# NRF51822_schematic.net
KiCad netlist of a schematic drawn in Altium Designer
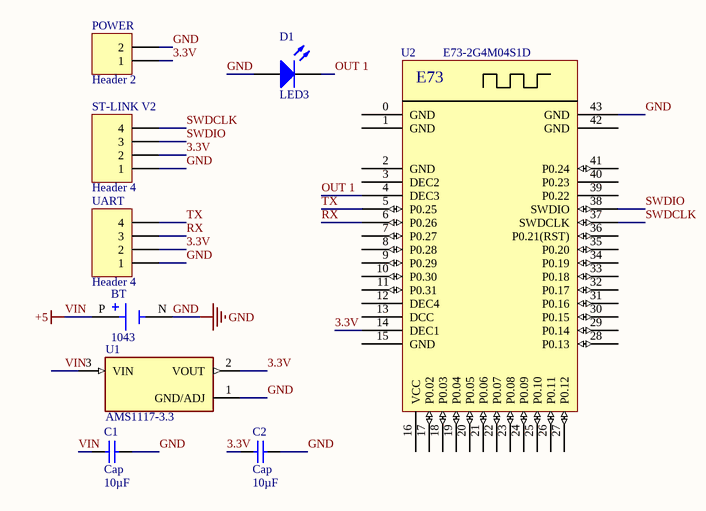
[diagram p0: NRF51822 schematic.SchDoc]

(export (version "E")
  (design (tool "Eeschema 10.0.6"))
  (components
    (comp (ref "BT")
      (value "1043")
      (footprint "BAT_1043")
      (description "THM Holder for 18650 Battery")
      (fields (field (name "MF") "Keystone Electronics"))
      (libsource (lib "1043") (part "1043"))
    )
    (comp (ref "C1")
      (value "Cap")
      (footprint "RAD-0.3")
      (description "Capacitor")
      (fields (field (name "ALTIUM_VALUE") "10µF") (field (name "PUBLISHER") "Altium Limited"))
      (libsource (lib "Miscellaneous Devices") (part "Cap"))
    )
    (comp (ref "C2")
      (value "Cap")
      (footprint "RAD-0.3")
      (description "Capacitor")
      (fields (field (name "ALTIUM_VALUE") "10µF") (field (name "PUBLISHER") "Altium Limited"))
      (libsource (lib "Miscellaneous Devices") (part "Cap"))
    )
    (comp (ref "D1")
      (value "LED3")
      (footprint "3.5X2.8X1.9")
      (description "Typical BLUE SiC LED")
      (fields (field (name "PUBLISHER") "Altium Limited"))
      (libsource (lib "Miscellaneous Devices") (part "LED3"))
    )
    (comp (ref "POWER")
      (value "Header 2")
      (footprint "HDR1X2")
      (description "Header, 2-Pin")
      (fields (field (name "PUBLISHER") "Altium Limited"))
      (libsource (lib "Miscellaneous Connectors") (part "Header 2"))
    )
    (comp (ref "ST-LINK V2")
      (value "Header 4")
      (footprint "HDR1X4")
      (description "Header, 4-Pin")
      (fields (field (name "PUBLISHER") "Altium Limited"))
      (libsource (lib "Miscellaneous Connectors") (part "Header 4"))
    )
    (comp (ref "U1")
      (value "AMS1117-3.3")
      (footprint "SOT229P700X180-4N")
      (description "Sot223/Pkg 1-Amp 3.3-Volt Low Drop Out Voltage Regulatator")
      (fields (field (name "MF") "Advanced Monolithic Systems"))
      (libsource (lib "AMS1117-3.3") (part "AMS1117-3.3"))
    )
    (comp (ref "U2")
      (value "E73-2G4M04S1D")
      (footprint "E73-2G4M04S1D")
      (libsource (lib "E73-2G4M04S1D-Chengdu Ebyte Electronic Technology-Symbol-Altium-19183") (part "E73-2G4M04S1D"))
    )
    (comp (ref "UART")
      (value "Header 4")
      (footprint "HDR1X4")
      (description "Header, 4-Pin")
      (fields (field (name "PUBLISHER") "Altium Limited"))
      (libsource (lib "Miscellaneous Connectors") (part "Header 4"))
    )
  )
  (nets
    (net (code "1") (name "+5") (class "Default")
      (node (ref "BT") (pin "P") (pinfunction "POS_P") (pintype "passive"))
      (node (ref "C1") (pin "1") (pinfunction "1_1") (pintype "passive"))
      (node (ref "U1") (pin "3") (pinfunction "VIN_3") (pintype "input"))
    )
    (net (code "2") (name "/3.3V") (class "Default")
      (node (ref "C2") (pin "1") (pinfunction "1_1") (pintype "passive"))
      (node (ref "POWER") (pin "1") (pinfunction "1_1") (pintype "passive"))
      (node (ref "ST-LINK V2") (pin "2") (pinfunction "2_2") (pintype "passive"))
      (node (ref "U1") (pin "2") (pinfunction "VOUT_2") (pintype "output"))
      (node (ref "U2") (pin "14") (pinfunction "DEC1_14") (pintype "passive"))
      (node (ref "UART") (pin "2") (pinfunction "2_2") (pintype "passive"))
    )
    (net (code "4") (name "/OUT 1") (class "Default")
      (node (ref "D1") (pin "2") (pinfunction "K_2") (pintype "passive"))
      (node (ref "U2") (pin "4") (pinfunction "DEC3_4") (pintype "passive"))
    )
    (net (code "5") (name "/RX") (class "Default")
      (node (ref "U2") (pin "6") (pinfunction "P0.26_6") (pintype "bidirectional"))
      (node (ref "UART") (pin "3") (pinfunction "3_3") (pintype "passive"))
    )
    (net (code "6") (name "/SWDCLK") (class "Default")
      (node (ref "ST-LINK V2") (pin "4") (pinfunction "4_4") (pintype "passive"))
      (node (ref "U2") (pin "37") (pinfunction "SWDCLK_37") (pintype "bidirectional"))
    )
    (net (code "7") (name "/SWDIO") (class "Default")
      (node (ref "ST-LINK V2") (pin "3") (pinfunction "3_3") (pintype "passive"))
      (node (ref "U2") (pin "38") (pinfunction "SWDIO_38") (pintype "bidirectional"))
    )
    (net (code "8") (name "/TX") (class "Default")
      (node (ref "U2") (pin "5") (pinfunction "P0.25_5") (pintype "bidirectional"))
      (node (ref "UART") (pin "4") (pinfunction "4_4") (pintype "passive"))
    )
    (net (code "9") (name "GND") (class "Default")
      (node (ref "BT") (pin "N") (pinfunction "NEG_N") (pintype "passive"))
      (node (ref "C1") (pin "2") (pinfunction "2_2") (pintype "passive"))
      (node (ref "C2") (pin "2") (pinfunction "2_2") (pintype "passive"))
      (node (ref "D1") (pin "1") (pinfunction "A_1") (pintype "passive"))
      (node (ref "POWER") (pin "2") (pinfunction "2_2") (pintype "passive"))
      (node (ref "ST-LINK V2") (pin "1") (pinfunction "1_1") (pintype "passive"))
      (node (ref "U1") (pin "1") (pinfunction "GND/ADJ_1") (pintype "power_in"))
      (node (ref "U2") (pin "43") (pinfunction "GND_43") (pintype "passive"))
      (node (ref "UART") (pin "1") (pinfunction "1_1") (pintype "passive"))
    )
    (net (code "10") (name "unconnected-(U2-DCC-Pad13)") (class "Default")
      (node (ref "U2") (pin "13") (pinfunction "DCC_13") (pintype "passive"))
    )
    (net (code "11") (name "unconnected-(U2-DEC2-Pad3)") (class "Default")
      (node (ref "U2") (pin "3") (pinfunction "DEC2_3") (pintype "passive"))
    )
    (net (code "12") (name "unconnected-(U2-DEC4-Pad12)") (class "Default")
      (node (ref "U2") (pin "12") (pinfunction "DEC4_12") (pintype "passive"))
    )
    (net (code "13") (name "unconnected-(U2-GND-Pad0)") (class "Default")
      (node (ref "U2") (pin "0") (pinfunction "GND_0") (pintype "passive"))
    )
    (net (code "14") (name "unconnected-(U2-GND-Pad1)") (class "Default")
      (node (ref "U2") (pin "1") (pinfunction "GND_1") (pintype "passive"))
    )
    (net (code "15") (name "unconnected-(U2-GND-Pad2)") (class "Default")
      (node (ref "U2") (pin "2") (pinfunction "GND_2") (pintype "passive"))
    )
    (net (code "16") (name "unconnected-(U2-GND-Pad15)") (class "Default")
      (node (ref "U2") (pin "15") (pinfunction "GND_15") (pintype "passive"))
    )
    (net (code "17") (name "unconnected-(U2-GND-Pad42)") (class "Default")
      (node (ref "U2") (pin "42") (pinfunction "GND_42") (pintype "passive"))
    )
    (net (code "18") (name "unconnected-(U2-P0.02-Pad17)") (class "Default")
      (node (ref "U2") (pin "17") (pinfunction "P0.02_17") (pintype "bidirectional"))
    )
    (net (code "19") (name "unconnected-(U2-P0.03-Pad18)") (class "Default")
      (node (ref "U2") (pin "18") (pinfunction "P0.03_18") (pintype "bidirectional"))
    )
    (net (code "20") (name "unconnected-(U2-P0.04-Pad19)") (class "Default")
      (node (ref "U2") (pin "19") (pinfunction "P0.04_19") (pintype "bidirectional"))
    )
    (net (code "21") (name "unconnected-(U2-P0.05-Pad20)") (class "Default")
      (node (ref "U2") (pin "20") (pinfunction "P0.05_20") (pintype "bidirectional"))
    )
    (net (code "22") (name "unconnected-(U2-P0.06-Pad21)") (class "Default")
      (node (ref "U2") (pin "21") (pinfunction "P0.06_21") (pintype "bidirectional"))
    )
    (net (code "23") (name "unconnected-(U2-P0.07-Pad22)") (class "Default")
      (node (ref "U2") (pin "22") (pinfunction "P0.07_22") (pintype "bidirectional"))
    )
    (net (code "24") (name "unconnected-(U2-P0.08-Pad23)") (class "Default")
      (node (ref "U2") (pin "23") (pinfunction "P0.08_23") (pintype "bidirectional"))
    )
    (net (code "25") (name "unconnected-(U2-P0.09-Pad24)") (class "Default")
      (node (ref "U2") (pin "24") (pinfunction "P0.09_24") (pintype "bidirectional"))
    )
    (net (code "26") (name "unconnected-(U2-P0.10-Pad25)") (class "Default")
      (node (ref "U2") (pin "25") (pinfunction "P0.10_25") (pintype "bidirectional"))
    )
    (net (code "27") (name "unconnected-(U2-P0.11-Pad26)") (class "Default")
      (node (ref "U2") (pin "26") (pinfunction "P0.11_26") (pintype "bidirectional"))
    )
    (net (code "28") (name "unconnected-(U2-P0.12-Pad27)") (class "Default")
      (node (ref "U2") (pin "27") (pinfunction "P0.12_27") (pintype "bidirectional"))
    )
    (net (code "29") (name "unconnected-(U2-P0.13-Pad28)") (class "Default")
      (node (ref "U2") (pin "28") (pinfunction "P0.13_28") (pintype "bidirectional"))
    )
    (net (code "30") (name "unconnected-(U2-P0.14-Pad29)") (class "Default")
      (node (ref "U2") (pin "29") (pinfunction "P0.14_29") (pintype "bidirectional"))
    )
    (net (code "31") (name "unconnected-(U2-P0.15-Pad30)") (class "Default")
      (node (ref "U2") (pin "30") (pinfunction "P0.15_30") (pintype "bidirectional"))
    )
    (net (code "32") (name "unconnected-(U2-P0.16-Pad31)") (class "Default")
      (node (ref "U2") (pin "31") (pinfunction "P0.16_31") (pintype "bidirectional"))
    )
    (net (code "33") (name "unconnected-(U2-P0.17-Pad32)") (class "Default")
      (node (ref "U2") (pin "32") (pinfunction "P0.17_32") (pintype "bidirectional"))
    )
    (net (code "34") (name "unconnected-(U2-P0.18-Pad33)") (class "Default")
      (node (ref "U2") (pin "33") (pinfunction "P0.18_33") (pintype "bidirectional"))
    )
    (net (code "35") (name "unconnected-(U2-P0.19-Pad34)") (class "Default")
      (node (ref "U2") (pin "34") (pinfunction "P0.19_34") (pintype "bidirectional"))
    )
    (net (code "36") (name "unconnected-(U2-P0.20-Pad35)") (class "Default")
      (node (ref "U2") (pin "35") (pinfunction "P0.20_35") (pintype "bidirectional"))
    )
    (net (code "37") (name "unconnected-(U2-P0.21(RST)-Pad36)") (class "Default")
      (node (ref "U2") (pin "36") (pinfunction "P0.21(RST)_36") (pintype "bidirectional"))
    )
    (net (code "38") (name "unconnected-(U2-P0.22-Pad39)") (class "Default")
      (node (ref "U2") (pin "39") (pinfunction "P0.22_39") (pintype "passive"))
    )
    (net (code "39") (name "unconnected-(U2-P0.23-Pad40)") (class "Default")
      (node (ref "U2") (pin "40") (pinfunction "P0.23_40") (pintype "passive"))
    )
    (net (code "40") (name "unconnected-(U2-P0.24-Pad41)") (class "Default")
      (node (ref "U2") (pin "41") (pinfunction "P0.24_41") (pintype "bidirectional"))
    )
    (net (code "41") (name "unconnected-(U2-P0.27-Pad7)") (class "Default")
      (node (ref "U2") (pin "7") (pinfunction "P0.27_7") (pintype "bidirectional"))
    )
    (net (code "42") (name "unconnected-(U2-P0.28-Pad8)") (class "Default")
      (node (ref "U2") (pin "8") (pinfunction "P0.28_8") (pintype "bidirectional"))
    )
    (net (code "43") (name "unconnected-(U2-P0.29-Pad9)") (class "Default")
      (node (ref "U2") (pin "9") (pinfunction "P0.29_9") (pintype "bidirectional"))
    )
    (net (code "44") (name "unconnected-(U2-P0.30-Pad10)") (class "Default")
      (node (ref "U2") (pin "10") (pinfunction "P0.30_10") (pintype "bidirectional"))
    )
    (net (code "45") (name "unconnected-(U2-P0.31-Pad11)") (class "Default")
      (node (ref "U2") (pin "11") (pinfunction "P0.31_11") (pintype "bidirectional"))
    )
    (net (code "46") (name "unconnected-(U2-VCC-Pad16)") (class "Default")
      (node (ref "U2") (pin "16") (pinfunction "VCC_16") (pintype "passive"))
    )
  )
)
